# bvm.net
KiCad netlist of a schematic drawn in EAGLE
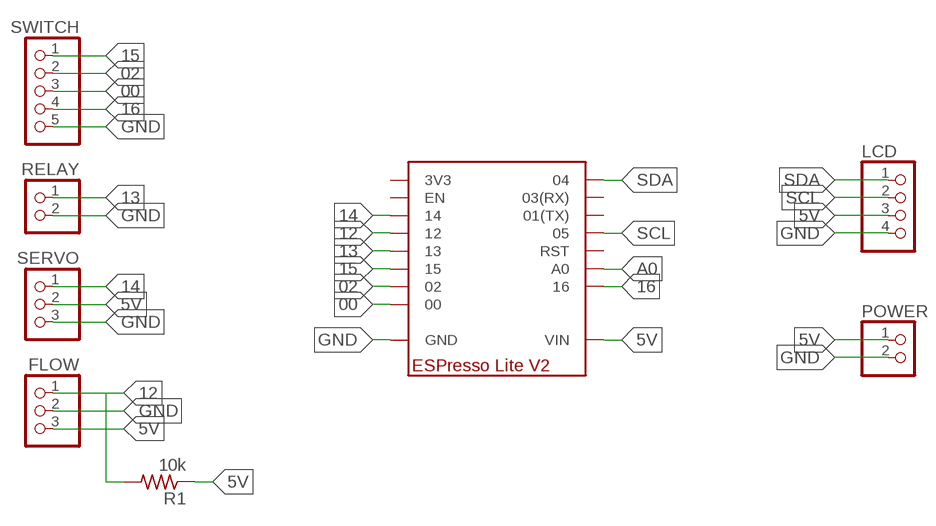
[diagram p0: schematic, sheet 1]

(export (version "E")
  (design (tool "Eeschema 10.0.6"))
  (components
    (comp (ref "FLOW")
      (value "PINHD-1X3")
      (footprint "eagle-import:1X03")
      (libsource (lib "eagle-import") (part "PINHD-1X3"))
    )
    (comp (ref "LCD")
      (value "PINHD-1X4")
      (footprint "eagle-import:1X04")
      (libsource (lib "eagle-import") (part "PINHD-1X4"))
    )
    (comp (ref "POWER")
      (value "PINHD-1X2")
      (footprint "eagle-import:1X02")
      (libsource (lib "eagle-import") (part "PINHD-1X2"))
    )
    (comp (ref "R1")
      (value "10k")
      (footprint "eagle-import:0207_10")
      (libsource (lib "eagle-import") (part "R-US_0207/10"))
    )
    (comp (ref "RELAY")
      (value "PINHD-1X2")
      (footprint "eagle-import:1X02")
      (libsource (lib "eagle-import") (part "PINHD-1X2"))
    )
    (comp (ref "SERVO")
      (value "PINHD-1X3")
      (footprint "eagle-import:1X03")
      (libsource (lib "eagle-import") (part "PINHD-1X3"))
    )
    (comp (ref "SWITCH")
      (value "PINHD-1X5")
      (footprint "eagle-import:1X05")
      (libsource (lib "eagle-import") (part "PINHD-1X5"))
    )
    (comp (ref "U$1")
      (value "ESPRESSO-LITE-V2")
      (footprint "eagle-import:ESPRESSO-LITE-V2")
      (libsource (lib "eagle-import") (part "ESPRESSO-LITE-V2"))
    )
  )
  (nets
    (net (code "1") (name "00") (class "Default")
      (node (ref "SWITCH") (pin "3") (pinfunction "3_3") (pintype "passive"))
      (node (ref "U$1") (pin "00") (pinfunction "00_00") (pintype "bidirectional"))
    )
    (net (code "2") (name "02") (class "Default")
      (node (ref "SWITCH") (pin "2") (pinfunction "2_2") (pintype "passive"))
      (node (ref "U$1") (pin "02") (pinfunction "02_02") (pintype "bidirectional"))
    )
    (net (code "3") (name "5V") (class "Default")
      (node (ref "FLOW") (pin "3") (pinfunction "3_3") (pintype "passive"))
      (node (ref "LCD") (pin "3") (pinfunction "3_3") (pintype "passive"))
      (node (ref "POWER") (pin "1") (pinfunction "1_1") (pintype "passive"))
      (node (ref "R1") (pin "1") (pinfunction "1_1") (pintype "passive"))
      (node (ref "SERVO") (pin "2") (pinfunction "2_2") (pintype "passive"))
      (node (ref "U$1") (pin "VIN1") (pinfunction "VIN_VIN1") (pintype "bidirectional"))
      (node (ref "U$1") (pin "VIN2") (pinfunction "VIN_VIN2") (pintype "bidirectional"))
    )
    (net (code "4") (name "12") (class "Default")
      (node (ref "FLOW") (pin "1") (pinfunction "1_1") (pintype "passive"))
      (node (ref "R1") (pin "2") (pinfunction "2_2") (pintype "passive"))
      (node (ref "U$1") (pin "12") (pinfunction "12_12") (pintype "bidirectional"))
    )
    (net (code "5") (name "13") (class "Default")
      (node (ref "RELAY") (pin "1") (pinfunction "1_1") (pintype "passive"))
      (node (ref "U$1") (pin "13") (pinfunction "13_13") (pintype "bidirectional"))
    )
    (net (code "6") (name "14") (class "Default")
      (node (ref "SERVO") (pin "1") (pinfunction "1_1") (pintype "passive"))
      (node (ref "U$1") (pin "14") (pinfunction "14_14") (pintype "bidirectional"))
    )
    (net (code "7") (name "15") (class "Default")
      (node (ref "SWITCH") (pin "1") (pinfunction "1_1") (pintype "passive"))
      (node (ref "U$1") (pin "15") (pinfunction "15_15") (pintype "bidirectional"))
    )
    (net (code "8") (name "16") (class "Default")
      (node (ref "SWITCH") (pin "4") (pinfunction "4_4") (pintype "passive"))
      (node (ref "U$1") (pin "16") (pinfunction "16_16") (pintype "bidirectional"))
    )
    (net (code "9") (name "A0") (class "Default")
      (node (ref "U$1") (pin "AO") (pinfunction "A0_AO") (pintype "bidirectional"))
    )
    (net (code "10") (name "GND") (class "Default")
      (node (ref "FLOW") (pin "2") (pinfunction "2_2") (pintype "passive"))
      (node (ref "LCD") (pin "4") (pinfunction "4_4") (pintype "passive"))
      (node (ref "POWER") (pin "2") (pinfunction "2_2") (pintype "passive"))
      (node (ref "RELAY") (pin "2") (pinfunction "2_2") (pintype "passive"))
      (node (ref "SERVO") (pin "3") (pinfunction "3_3") (pintype "passive"))
      (node (ref "SWITCH") (pin "5") (pinfunction "5_5") (pintype "passive"))
      (node (ref "U$1") (pin "GND1") (pinfunction "GND_GND1") (pintype "bidirectional"))
      (node (ref "U$1") (pin "GND2") (pinfunction "GND_GND2") (pintype "bidirectional"))
      (node (ref "U$1") (pin "GND3") (pinfunction "GND_GND3") (pintype "bidirectional"))
    )
    (net (code "11") (name "SCL") (class "Default")
      (node (ref "LCD") (pin "2") (pinfunction "2_2") (pintype "passive"))
      (node (ref "U$1") (pin "05") (pinfunction "05_05") (pintype "bidirectional"))
    )
    (net (code "12") (name "SDA") (class "Default")
      (node (ref "LCD") (pin "1") (pinfunction "1_1") (pintype "passive"))
      (node (ref "U$1") (pin "04") (pinfunction "04_04") (pintype "bidirectional"))
    )
    (net (code "13") (name "unconnected-(U$1-01(TX)-Pad01)") (class "Default")
      (node (ref "U$1") (pin "01") (pinfunction "01(TX)_01") (pintype "bidirectional"))
    )
    (net (code "14") (name "unconnected-(U$1-03(RX)-Pad03)") (class "Default")
      (node (ref "U$1") (pin "03") (pinfunction "03(RX)_03") (pintype "bidirectional"))
    )
    (net (code "15") (name "unconnected-(U$1-Pad3V3)") (class "Default")
      (node (ref "U$1") (pin "3V3") (pinfunction "3V3_3V3") (pintype "bidirectional"))
    )
    (net (code "16") (name "unconnected-(U$1-PadEN)") (class "Default")
      (node (ref "U$1") (pin "EN") (pinfunction "EN_EN") (pintype "bidirectional"))
    )
    (net (code "17") (name "unconnected-(U$1-PadRST)") (class "Default")
      (node (ref "U$1") (pin "RST") (pinfunction "RST_RST") (pintype "bidirectional"))
    )
  )
)
